# Schematic.net
KiCad netlist of a schematic drawn in EAGLE
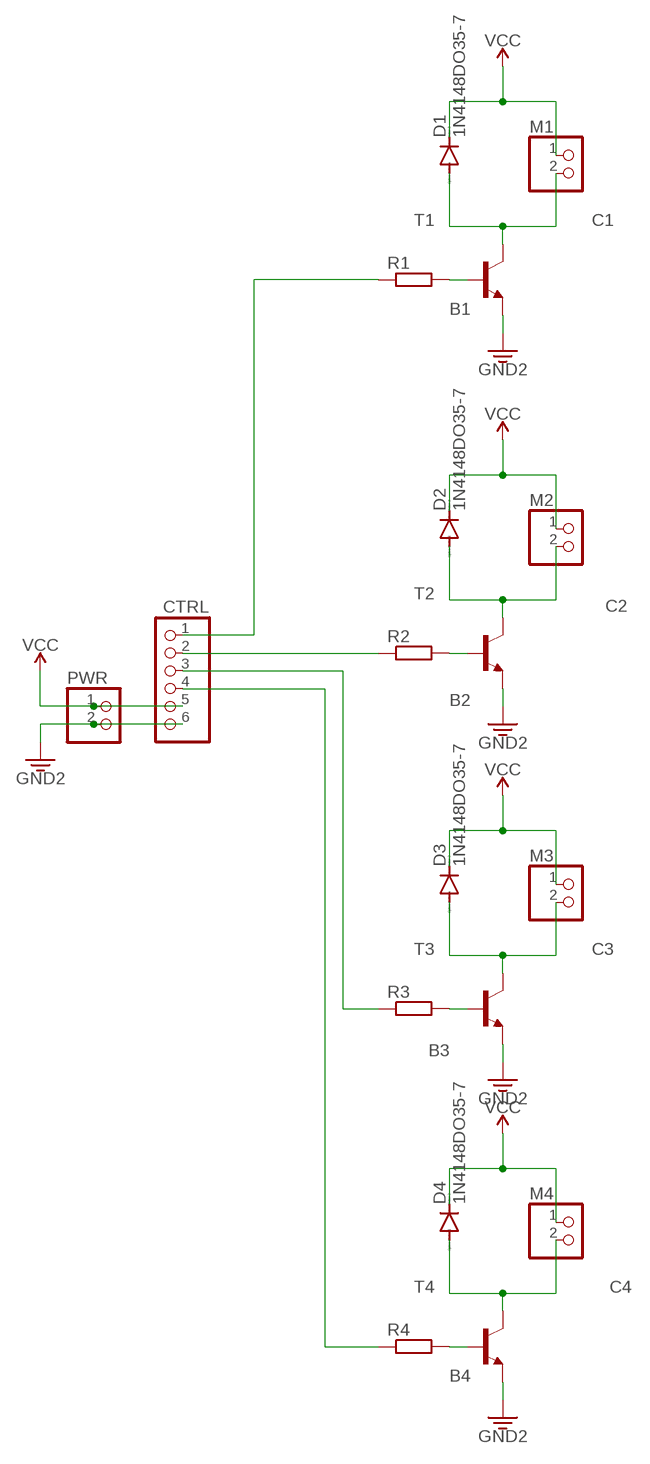
[diagram p0: schematic, sheet 1]

(export (version "E")
  (design (tool "Eeschema 10.0.6"))
  (components
    (comp (ref "CTRL")
      (value "PINHD-1X6")
      (footprint "eagle-import:1X06")
      (libsource (lib "eagle-import") (part "PINHD-1X6"))
    )
    (comp (ref "D1")
      (value "1N4148DO35-7")
      (footprint "eagle-import:DO35-7")
      (libsource (lib "eagle-import") (part "1N4148DO35-7"))
    )
    (comp (ref "D2")
      (value "1N4148DO35-7")
      (footprint "eagle-import:DO35-7")
      (libsource (lib "eagle-import") (part "1N4148DO35-7"))
    )
    (comp (ref "D3")
      (value "1N4148DO35-7")
      (footprint "eagle-import:DO35-7")
      (libsource (lib "eagle-import") (part "1N4148DO35-7"))
    )
    (comp (ref "D4")
      (value "1N4148DO35-7")
      (footprint "eagle-import:DO35-7")
      (libsource (lib "eagle-import") (part "1N4148DO35-7"))
    )
    (comp (ref "M1")
      (value "PINHD-1X2")
      (footprint "eagle-import:1X02")
      (libsource (lib "eagle-import") (part "PINHD-1X2"))
    )
    (comp (ref "M2")
      (value "PINHD-1X2")
      (footprint "eagle-import:1X02")
      (libsource (lib "eagle-import") (part "PINHD-1X2"))
    )
    (comp (ref "M3")
      (value "PINHD-1X2")
      (footprint "eagle-import:1X02")
      (libsource (lib "eagle-import") (part "PINHD-1X2"))
    )
    (comp (ref "M4")
      (value "PINHD-1X2")
      (footprint "eagle-import:1X02")
      (libsource (lib "eagle-import") (part "PINHD-1X2"))
    )
    (comp (ref "PWR")
      (value "PINHD-1X2")
      (footprint "eagle-import:1X02")
      (libsource (lib "eagle-import") (part "PINHD-1X2"))
    )
    (comp (ref "R1")
      (value "R-EU_R0805")
      (footprint "eagle-import:R0805")
      (libsource (lib "eagle-import") (part "R-EU_R0805"))
    )
    (comp (ref "R2")
      (value "R-EU_R0805")
      (footprint "eagle-import:R0805")
      (libsource (lib "eagle-import") (part "R-EU_R0805"))
    )
    (comp (ref "R3")
      (value "R-EU_R0805")
      (footprint "eagle-import:R0805")
      (libsource (lib "eagle-import") (part "R-EU_R0805"))
    )
    (comp (ref "R4")
      (value "R-EU_R0805")
      (footprint "eagle-import:R0805")
      (libsource (lib "eagle-import") (part "R-EU_R0805"))
    )
    (comp (ref "T1")
      (value "2N2222-NPN-TO92-EBC")
      (footprint "eagle-import:TO92-EBC")
      (libsource (lib "eagle-import") (part "-NPN-TO92-EBC2N2222"))
    )
    (comp (ref "T2")
      (value "2N2222-NPN-TO92-EBC")
      (footprint "eagle-import:TO92-EBC")
      (libsource (lib "eagle-import") (part "-NPN-TO92-EBC2N2222"))
    )
    (comp (ref "T3")
      (value "2N2222-NPN-TO92-EBC")
      (footprint "eagle-import:TO92-EBC")
      (libsource (lib "eagle-import") (part "-NPN-TO92-EBC2N2222"))
    )
    (comp (ref "T4")
      (value "2N2222-NPN-TO92-EBC")
      (footprint "eagle-import:TO92-EBC")
      (libsource (lib "eagle-import") (part "-NPN-TO92-EBC2N2222"))
    )
  )
  (nets
    (net (code "1") (name "/B1") (class "Default")
      (node (ref "R1") (pin "2") (pinfunction "2_2") (pintype "passive"))
      (node (ref "T1") (pin "B") (pinfunction "B_B") (pintype "passive"))
    )
    (net (code "2") (name "/B2") (class "Default")
      (node (ref "R2") (pin "2") (pinfunction "2_2") (pintype "passive"))
      (node (ref "T2") (pin "B") (pinfunction "B_B") (pintype "passive"))
    )
    (net (code "3") (name "/B3") (class "Default")
      (node (ref "R3") (pin "2") (pinfunction "2_2") (pintype "passive"))
      (node (ref "T3") (pin "B") (pinfunction "B_B") (pintype "passive"))
    )
    (net (code "4") (name "/B4") (class "Default")
      (node (ref "R4") (pin "2") (pinfunction "2_2") (pintype "passive"))
      (node (ref "T4") (pin "B") (pinfunction "B_B") (pintype "passive"))
    )
    (net (code "5") (name "/C1") (class "Default")
      (node (ref "D1") (pin "A") (pinfunction "A_A") (pintype "passive"))
      (node (ref "M1") (pin "2") (pinfunction "2_2") (pintype "passive"))
      (node (ref "T1") (pin "C") (pinfunction "C_C") (pintype "passive"))
    )
    (net (code "6") (name "/C2") (class "Default")
      (node (ref "D2") (pin "A") (pinfunction "A_A") (pintype "passive"))
      (node (ref "M2") (pin "2") (pinfunction "2_2") (pintype "passive"))
      (node (ref "T2") (pin "C") (pinfunction "C_C") (pintype "passive"))
    )
    (net (code "7") (name "/C3") (class "Default")
      (node (ref "D3") (pin "A") (pinfunction "A_A") (pintype "passive"))
      (node (ref "M3") (pin "2") (pinfunction "2_2") (pintype "passive"))
      (node (ref "T3") (pin "C") (pinfunction "C_C") (pintype "passive"))
    )
    (net (code "8") (name "/C4") (class "Default")
      (node (ref "D4") (pin "A") (pinfunction "A_A") (pintype "passive"))
      (node (ref "M4") (pin "2") (pinfunction "2_2") (pintype "passive"))
      (node (ref "T4") (pin "C") (pinfunction "C_C") (pintype "passive"))
    )
    (net (code "9") (name "GND2") (class "Default")
      (node (ref "CTRL") (pin "6") (pinfunction "6_6") (pintype "passive"))
      (node (ref "PWR") (pin "2") (pinfunction "2_2") (pintype "passive"))
      (node (ref "T1") (pin "E") (pinfunction "E_E") (pintype "passive"))
      (node (ref "T2") (pin "E") (pinfunction "E_E") (pintype "passive"))
      (node (ref "T3") (pin "E") (pinfunction "E_E") (pintype "passive"))
      (node (ref "T4") (pin "E") (pinfunction "E_E") (pintype "passive"))
    )
    (net (code "10") (name "Net-(CTRL-Pad1)") (class "Default")
      (node (ref "CTRL") (pin "1") (pinfunction "1_1") (pintype "passive"))
      (node (ref "R1") (pin "1") (pinfunction "1_1") (pintype "passive"))
    )
    (net (code "11") (name "Net-(CTRL-Pad2)") (class "Default")
      (node (ref "CTRL") (pin "2") (pinfunction "2_2") (pintype "passive"))
      (node (ref "R2") (pin "1") (pinfunction "1_1") (pintype "passive"))
    )
    (net (code "12") (name "Net-(CTRL-Pad3)") (class "Default")
      (node (ref "CTRL") (pin "3") (pinfunction "3_3") (pintype "passive"))
      (node (ref "R3") (pin "1") (pinfunction "1_1") (pintype "passive"))
    )
    (net (code "13") (name "Net-(CTRL-Pad4)") (class "Default")
      (node (ref "CTRL") (pin "4") (pinfunction "4_4") (pintype "passive"))
      (node (ref "R4") (pin "1") (pinfunction "1_1") (pintype "passive"))
    )
    (net (code "14") (name "VCC") (class "Default")
      (node (ref "CTRL") (pin "5") (pinfunction "5_5") (pintype "passive"))
      (node (ref "D1") (pin "C") (pinfunction "C_C") (pintype "passive"))
      (node (ref "D2") (pin "C") (pinfunction "C_C") (pintype "passive"))
      (node (ref "D3") (pin "C") (pinfunction "C_C") (pintype "passive"))
      (node (ref "D4") (pin "C") (pinfunction "C_C") (pintype "passive"))
      (node (ref "M1") (pin "1") (pinfunction "1_1") (pintype "passive"))
      (node (ref "M2") (pin "1") (pinfunction "1_1") (pintype "passive"))
      (node (ref "M3") (pin "1") (pinfunction "1_1") (pintype "passive"))
      (node (ref "M4") (pin "1") (pinfunction "1_1") (pintype "passive"))
      (node (ref "PWR") (pin "1") (pinfunction "1_1") (pintype "passive"))
    )
  )
)
